# Sheet1.net
KiCad netlist of a schematic drawn in Altium Designer
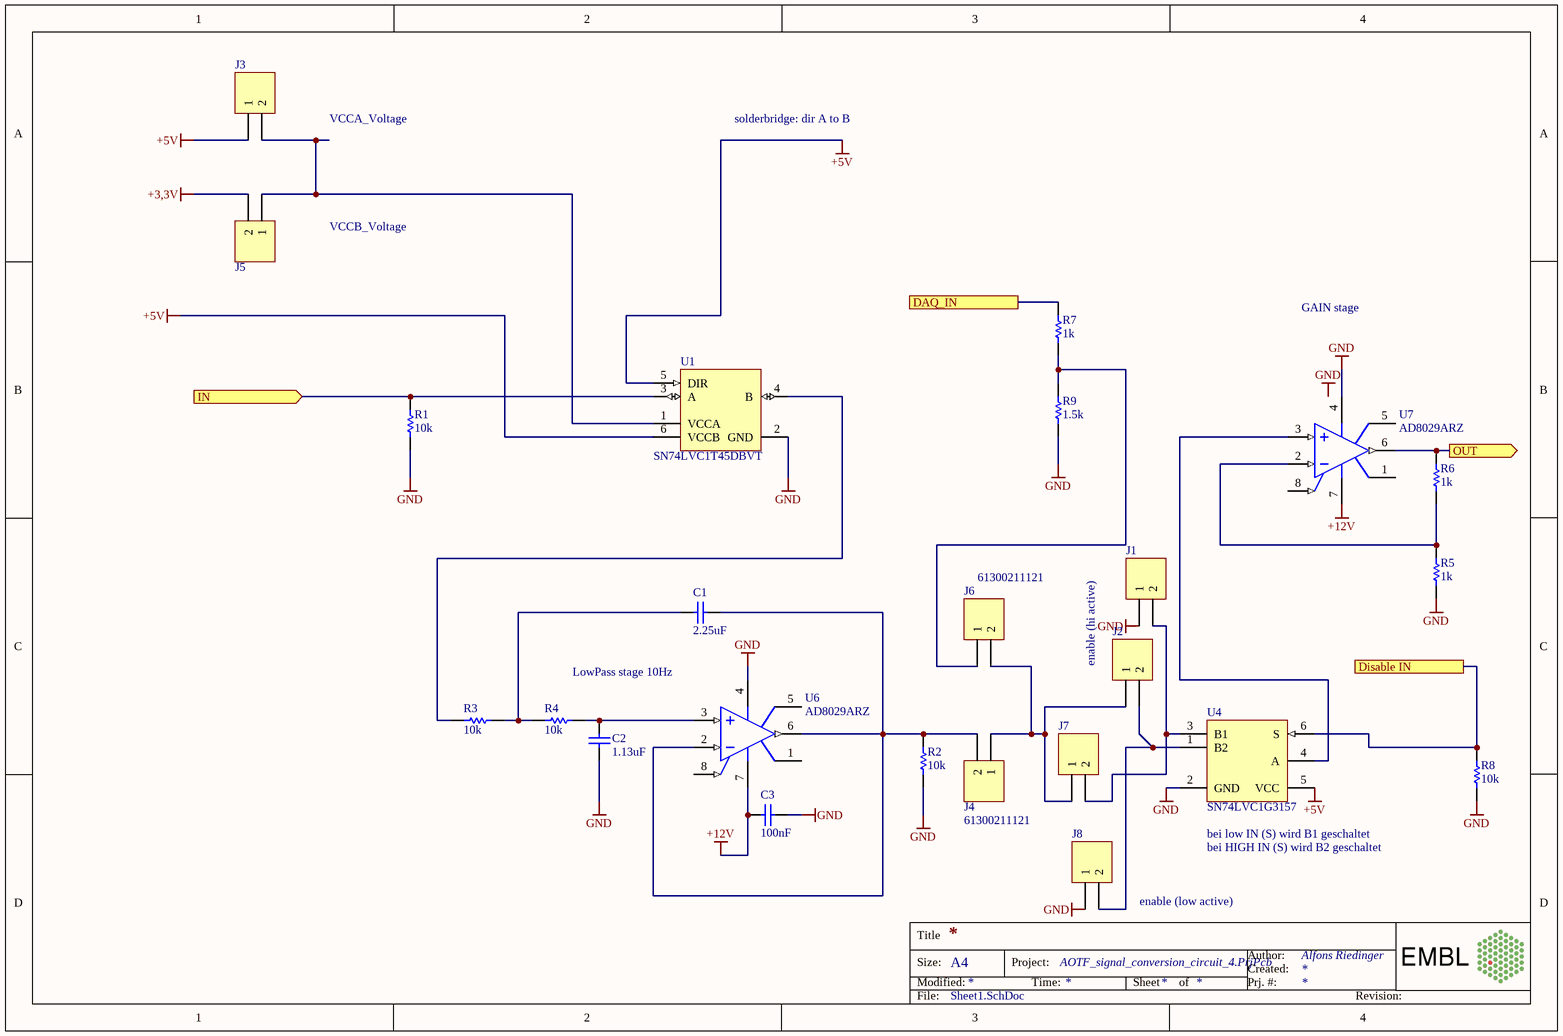
[diagram p0: Sheet1.SchDoc]

(export (version "E")
  (design (tool "Eeschema 10.0.6"))
  (components
    (comp (ref "C1")
      (value "2.25uF")
      (footprint "CAPC1206(3216)190_N")
      (description "CAP CER 1UF 10V X7R 1206")
      (fields
        (field (name "MANUFACTURER") "Wurth Electronics Inc.")
        (field (name "MANUFACTURER PART NUMBER") "885012208013")
      )
      (libsource (lib "Altium Vault EMBL 3") (part "CMP-001-0138-A.1"))
    )
    (comp (ref "C2")
      (value "1.13uF")
      (footprint "CAPC1206(3216)190_N")
      (description "CAP CER 1UF 10V X7R 1206")
      (fields
        (field (name "MANUFACTURER") "Wurth Electronics Inc.")
        (field (name "MANUFACTURER PART NUMBER") "885012208013")
      )
      (libsource (lib "Altium Vault EMBL 3") (part "CMP-001-0138-A.1"))
    )
    (comp (ref "C3")
      (value "100nF")
      (footprint "CAPC2013X88X50ML20T25")
      (description "generic 0805 COG oder X7R Vielschichtkondensatoren max. +/-10%")
      (libsource (lib "Altium Vault EMBL") (part "CMP-001-0082-2"))
    )
    (comp (ref "J1")
      (value "61300211121")
      (footprint "61300211121")
      (description "2Pol; gerade; WR-PHD 2.54 mm THT Pin Header")
      (fields (field (name "MANUFACTURER") "Wurth Electronics"))
      (libsource (lib "Altium Vault EMBL 3") (part "CMP-001-0071-1"))
    )
    (comp (ref "J2")
      (value "61300211121")
      (footprint "61300211121")
      (description "2Pol; gerade; WR-PHD 2.54 mm THT Pin Header")
      (fields (field (name "MANUFACTURER") "Wurth Electronics"))
      (libsource (lib "Altium Vault EMBL 3") (part "CMP-001-0071-1"))
    )
    (comp (ref "J3")
      (value "61300211121")
      (footprint "61300211121")
      (description "2Pol; gerade; WR-PHD 2.54 mm THT Pin Header")
      (fields (field (name "MANUFACTURER") "Wurth Electronics"))
      (libsource (lib "Altium Vault EMBL 3") (part "CMP-001-0071-1"))
    )
    (comp (ref "J4")
      (value "61300211121")
      (footprint "61300211121")
      (description "2Pol; gerade; WR-PHD 2.54 mm THT Pin Header")
      (fields (field (name "MANUFACTURER") "Wurth Electronics"))
      (libsource (lib "") (part "CMP-001-0071-1_1"))
    )
    (comp (ref "J5")
      (value "61300211121")
      (footprint "61300211121")
      (description "2Pol; gerade; WR-PHD 2.54 mm THT Pin Header")
      (fields (field (name "MANUFACTURER") "Wurth Electronics"))
      (libsource (lib "") (part "CMP-001-0071-1_1"))
    )
    (comp (ref "J6")
      (value "61300211121")
      (footprint "61300211121")
      (description "2Pol; gerade; WR-PHD 2.54 mm THT Pin Header")
      (fields (field (name "MANUFACTURER") "Wurth Electronics"))
      (libsource (lib "Altium Vault EMBL 3") (part "CMP-001-0071-1"))
    )
    (comp (ref "J7")
      (value "61300211121")
      (footprint "61300211121")
      (description "2Pol; gerade; WR-PHD 2.54 mm THT Pin Header")
      (fields (field (name "MANUFACTURER") "Wurth Electronics"))
      (libsource (lib "Altium Vault EMBL 3") (part "CMP-001-0071-1"))
    )
    (comp (ref "J8")
      (value "61300211121")
      (footprint "61300211121")
      (description "2Pol; gerade; WR-PHD 2.54 mm THT Pin Header")
      (fields (field (name "MANUFACTURER") "Wurth Electronics"))
      (libsource (lib "Altium Vault EMBL 3") (part "CMP-001-0071-1"))
    )
    (comp (ref "R1")
      (value "10k")
      (footprint "YAGO-RC0805_M")
      (description "0805 Yageo Standard BlackBox Resistors")
      (fields (field (name "TOLERANCE") "±1%") (field (name "MANUFACTURER") "Yageo"))
      (libsource (lib "Altium Vault EMBL") (part "CMP-001-0027-2"))
    )
    (comp (ref "R2")
      (value "10k")
      (footprint "YAGO-RC0805_M")
      (description "0805 Yageo Standard BlackBox Resistors")
      (fields (field (name "TOLERANCE") "±1%") (field (name "MANUFACTURER") "Yageo"))
      (libsource (lib "Altium Vault EMBL") (part "CMP-001-0027-2"))
    )
    (comp (ref "R3")
      (value "10k")
      (footprint "YAGO-RC0805_M")
      (description "0805 Yageo Standard BlackBox Resistors")
      (fields (field (name "TOLERANCE") "±1%") (field (name "MANUFACTURER") "Yageo"))
      (libsource (lib "Altium Vault EMBL") (part "CMP-001-0027-2"))
    )
    (comp (ref "R4")
      (value "10k")
      (footprint "YAGO-RC0805_M")
      (description "0805 Yageo Standard BlackBox Resistors")
      (fields (field (name "TOLERANCE") "±1%") (field (name "MANUFACTURER") "Yageo"))
      (libsource (lib "Altium Vault EMBL") (part "CMP-001-0027-2"))
    )
    (comp (ref "R5")
      (value "1k")
      (footprint "YAGO-RC0805_M")
      (description "0805 Yageo Standard BlackBox Resistors")
      (fields (field (name "TOLERANCE") "±1%") (field (name "MANUFACTURER") "Yageo"))
      (libsource (lib "Altium Vault EMBL 3") (part "CMP-001-0027-2"))
    )
    (comp (ref "R6")
      (value "1k")
      (footprint "YAGO-RC0805_M")
      (description "0805 Yageo Standard BlackBox Resistors")
      (fields (field (name "TOLERANCE") "±1%") (field (name "MANUFACTURER") "Yageo"))
      (libsource (lib "Altium Vault EMBL 3") (part "CMP-001-0027-2"))
    )
    (comp (ref "R7")
      (value "1k")
      (footprint "YAGO-RC0805_M")
      (description "0805 Yageo Standard BlackBox Resistors")
      (fields (field (name "TOLERANCE") "±1%") (field (name "MANUFACTURER") "Yageo"))
      (libsource (lib "Altium Vault EMBL 3") (part "CMP-001-0027-2"))
    )
    (comp (ref "R8")
      (value "10k")
      (footprint "YAGO-RC0805_M")
      (description "0805 Yageo Standard BlackBox Resistors")
      (fields (field (name "TOLERANCE") "±1%") (field (name "MANUFACTURER") "Yageo"))
      (libsource (lib "Altium Vault EMBL") (part "CMP-001-0027-2"))
    )
    (comp (ref "R9")
      (value "1.5k")
      (footprint "YAGO-RC0805_M")
      (description "0805 Yageo Standard BlackBox Resistors")
      (fields (field (name "TOLERANCE") "±1%") (field (name "MANUFACTURER") "Yageo"))
      (libsource (lib "Altium Vault EMBL 3") (part "CMP-001-0027-2"))
    )
    (comp (ref "U1")
      (value "SN74LVC1T45DBVT")
      (footprint "DBV0006A_M")
      (fields
        (field (name "MANUFACTURER") "Texas Instruments")
        (field (name "GENERIC PART NUMBER") "SN74LVC1T45")
      )
      (libsource (lib "Altium Vault EMBL 3") (part "CMP-00491-1"))
    )
    (comp (ref "U4")
      (value "SN74LVC1G3157")
      (footprint "DBV0006A_N")
      (description "Analoger Schalter Single SPDT(Wechsler) SOT23-6")
      (fields
        (field (name "MANUFACTURER") "Texas Instruments")
        (field (name "MANUFACTURER PART NUMBER") "74LVC1G3157DBVRE4")
      )
      (libsource (lib "Altium Vault EMBL 3") (part "CMP-001-0106-A.1"))
    )
    (comp (ref "U6")
      (value "AD8029ARZ")
      (footprint "ADI-R-8_L")
      (fields (field (name "MANUFACTURER") "Analog Devices") (field (name "GENERIC PART NUMBER") "AD8029"))
      (libsource (lib "Altium Vault EMBL") (part "CMP-00480-1"))
    )
    (comp (ref "U7")
      (value "AD8029ARZ")
      (footprint "ADI-R-8_L")
      (fields (field (name "MANUFACTURER") "Analog Devices") (field (name "GENERIC PART NUMBER") "AD8029"))
      (libsource (lib "Altium Vault EMBL") (part "CMP-00480-1"))
    )
  )
  (nets
    (net (code "1") (name "+3,3V") (class "Default")
      (node (ref "J5") (pin "2") (pinfunction "2_2") (pintype "passive"))
    )
    (net (code "2") (name "+5V") (class "Default")
      (node (ref "J3") (pin "1") (pinfunction "1_1") (pintype "passive"))
      (node (ref "U1") (pin "5") (pinfunction "DIR_5") (pintype "input"))
      (node (ref "U1") (pin "6") (pinfunction "VCCB_6") (pintype "power_in"))
      (node (ref "U4") (pin "5") (pinfunction "VCC_5") (pintype "power_in"))
    )
    (net (code "3") (name "+12V") (class "Default")
      (node (ref "C3") (pin "2") (pinfunction "2_2") (pintype "passive"))
      (node (ref "U6") (pin "7") (pinfunction "+VS_7") (pintype "power_in"))
      (node (ref "U7") (pin "7") (pinfunction "+VS_7") (pintype "power_in"))
    )
    (net (code "4") (name "/DAQ_IN") (class "Default")
      (node (ref "R7") (pin "2") (pinfunction "2_2") (pintype "passive"))
    )
    (net (code "5") (name "/Disable IN") (class "Default")
      (node (ref "R8") (pin "1") (pinfunction "1_1") (pintype "passive"))
      (node (ref "U4") (pin "6") (pinfunction "S_6") (pintype "input"))
    )
    (net (code "6") (name "/IN") (class "Default")
      (node (ref "R1") (pin "2") (pinfunction "2_2") (pintype "passive"))
      (node (ref "U1") (pin "3") (pinfunction "A_3") (pintype "bidirectional"))
    )
    (net (code "7") (name "/OUT") (class "Default")
      (node (ref "R6") (pin "2") (pinfunction "2_2") (pintype "passive"))
      (node (ref "U7") (pin "6") (pinfunction "VOUT_6") (pintype "output"))
    )
    (net (code "8") (name "GND") (class "Default")
      (node (ref "C2") (pin "1") (pinfunction "1_1") (pintype "passive"))
      (node (ref "C3") (pin "1") (pinfunction "1_1") (pintype "passive"))
      (node (ref "J1") (pin "1") (pinfunction "1_1") (pintype "passive"))
      (node (ref "J8") (pin "1") (pinfunction "1_1") (pintype "passive"))
      (node (ref "R1") (pin "1") (pinfunction "1_1") (pintype "passive"))
      (node (ref "R2") (pin "1") (pinfunction "1_1") (pintype "passive"))
      (node (ref "R5") (pin "1") (pinfunction "1_1") (pintype "passive"))
      (node (ref "R8") (pin "2") (pinfunction "2_2") (pintype "passive"))
      (node (ref "R9") (pin "1") (pinfunction "1_1") (pintype "passive"))
      (node (ref "U1") (pin "2") (pinfunction "GND_2") (pintype "power_in"))
      (node (ref "U4") (pin "2") (pinfunction "GND_2") (pintype "power_in"))
      (node (ref "U6") (pin "4") (pinfunction "-VS_4") (pintype "power_in"))
      (node (ref "U7") (pin "4") (pinfunction "-VS_4") (pintype "power_in"))
    )
    (net (code "9") (name "Net-(C1-Pad1)") (class "Default")
      (node (ref "C1") (pin "1") (pinfunction "1_1") (pintype "passive"))
      (node (ref "R3") (pin "1") (pinfunction "1_1") (pintype "passive"))
      (node (ref "R4") (pin "2") (pinfunction "2_2") (pintype "passive"))
    )
    (net (code "10") (name "Net-(J2-Pad1)") (class "Default")
      (node (ref "J2") (pin "1") (pinfunction "1_1") (pintype "passive"))
      (node (ref "J4") (pin "1") (pinfunction "1_1") (pintype "passive"))
      (node (ref "J6") (pin "2") (pinfunction "2_2") (pintype "passive"))
      (node (ref "J7") (pin "1") (pinfunction "1_1") (pintype "passive"))
    )
    (net (code "11") (name "Net-(J6-Pad1)") (class "Default")
      (node (ref "J6") (pin "1") (pinfunction "1_1") (pintype "passive"))
      (node (ref "R7") (pin "1") (pinfunction "1_1") (pintype "passive"))
      (node (ref "R9") (pin "2") (pinfunction "2_2") (pintype "passive"))
    )
    (net (code "12") (name "Net-(U1-B)") (class "Default")
      (node (ref "R3") (pin "2") (pinfunction "2_2") (pintype "passive"))
      (node (ref "U1") (pin "4") (pinfunction "B_4") (pintype "bidirectional"))
    )
    (net (code "13") (name "Net-(U1-VCCA)") (class "Default")
      (node (ref "J3") (pin "2") (pinfunction "2_2") (pintype "passive"))
      (node (ref "J5") (pin "1") (pinfunction "1_1") (pintype "passive"))
      (node (ref "U1") (pin "1") (pinfunction "VCCA_1") (pintype "power_in"))
    )
    (net (code "14") (name "Net-(U4-A)") (class "Default")
      (node (ref "U4") (pin "4") (pinfunction "A_4") (pintype "passive"))
      (node (ref "U7") (pin "3") (pinfunction "+IN_3") (pintype "input"))
    )
    (net (code "15") (name "Net-(U4-B1)") (class "Default")
      (node (ref "J1") (pin "2") (pinfunction "2_2") (pintype "passive"))
      (node (ref "J7") (pin "2") (pinfunction "2_2") (pintype "passive"))
      (node (ref "U4") (pin "3") (pinfunction "B1_3") (pintype "passive"))
    )
    (net (code "16") (name "Net-(U4-B2)") (class "Default")
      (node (ref "J2") (pin "2") (pinfunction "2_2") (pintype "passive"))
      (node (ref "J8") (pin "2") (pinfunction "2_2") (pintype "passive"))
      (node (ref "U4") (pin "1") (pinfunction "B2_1") (pintype "passive"))
    )
    (net (code "17") (name "Net-(U6-+IN)") (class "Default")
      (node (ref "C2") (pin "2") (pinfunction "2_2") (pintype "passive"))
      (node (ref "R4") (pin "1") (pinfunction "1_1") (pintype "passive"))
      (node (ref "U6") (pin "3") (pinfunction "+IN_3") (pintype "input"))
    )
    (net (code "18") (name "Net-(U6--IN)") (class "Default")
      (node (ref "C1") (pin "2") (pinfunction "2_2") (pintype "passive"))
      (node (ref "J4") (pin "2") (pinfunction "2_2") (pintype "passive"))
      (node (ref "R2") (pin "2") (pinfunction "2_2") (pintype "passive"))
      (node (ref "U6") (pin "2") (pinfunction "-IN_2") (pintype "input"))
      (node (ref "U6") (pin "6") (pinfunction "VOUT_6") (pintype "output"))
    )
    (net (code "19") (name "Net-(U7--IN)") (class "Default")
      (node (ref "R5") (pin "2") (pinfunction "2_2") (pintype "passive"))
      (node (ref "R6") (pin "1") (pinfunction "1_1") (pintype "passive"))
      (node (ref "U7") (pin "2") (pinfunction "-IN_2") (pintype "input"))
    )
    (net (code "20") (name "unconnected-(U6-NC-Pad1)") (class "Default")
      (node (ref "U6") (pin "1") (pinfunction "NC_1") (pintype "passive"))
    )
    (net (code "21") (name "unconnected-(U6-NC-Pad5)") (class "Default")
      (node (ref "U6") (pin "5") (pinfunction "NC_5") (pintype "passive"))
    )
    (net (code "22") (name "unconnected-(U6-~{DISABLE}-Pad8)") (class "Default")
      (node (ref "U6") (pin "8") (pinfunction "~{DISABLE}_8") (pintype "input"))
    )
    (net (code "23") (name "unconnected-(U7-NC-Pad1)") (class "Default")
      (node (ref "U7") (pin "1") (pinfunction "NC_1") (pintype "passive"))
    )
    (net (code "24") (name "unconnected-(U7-NC-Pad5)") (class "Default")
      (node (ref "U7") (pin "5") (pinfunction "NC_5") (pintype "passive"))
    )
    (net (code "25") (name "unconnected-(U7-~{DISABLE}-Pad8)") (class "Default")
      (node (ref "U7") (pin "8") (pinfunction "~{DISABLE}_8") (pintype "input"))
    )
  )
)
